# Rectifire__PFC__Evaluation_Board.net
KiCad netlist of a schematic drawn in Altium Designer
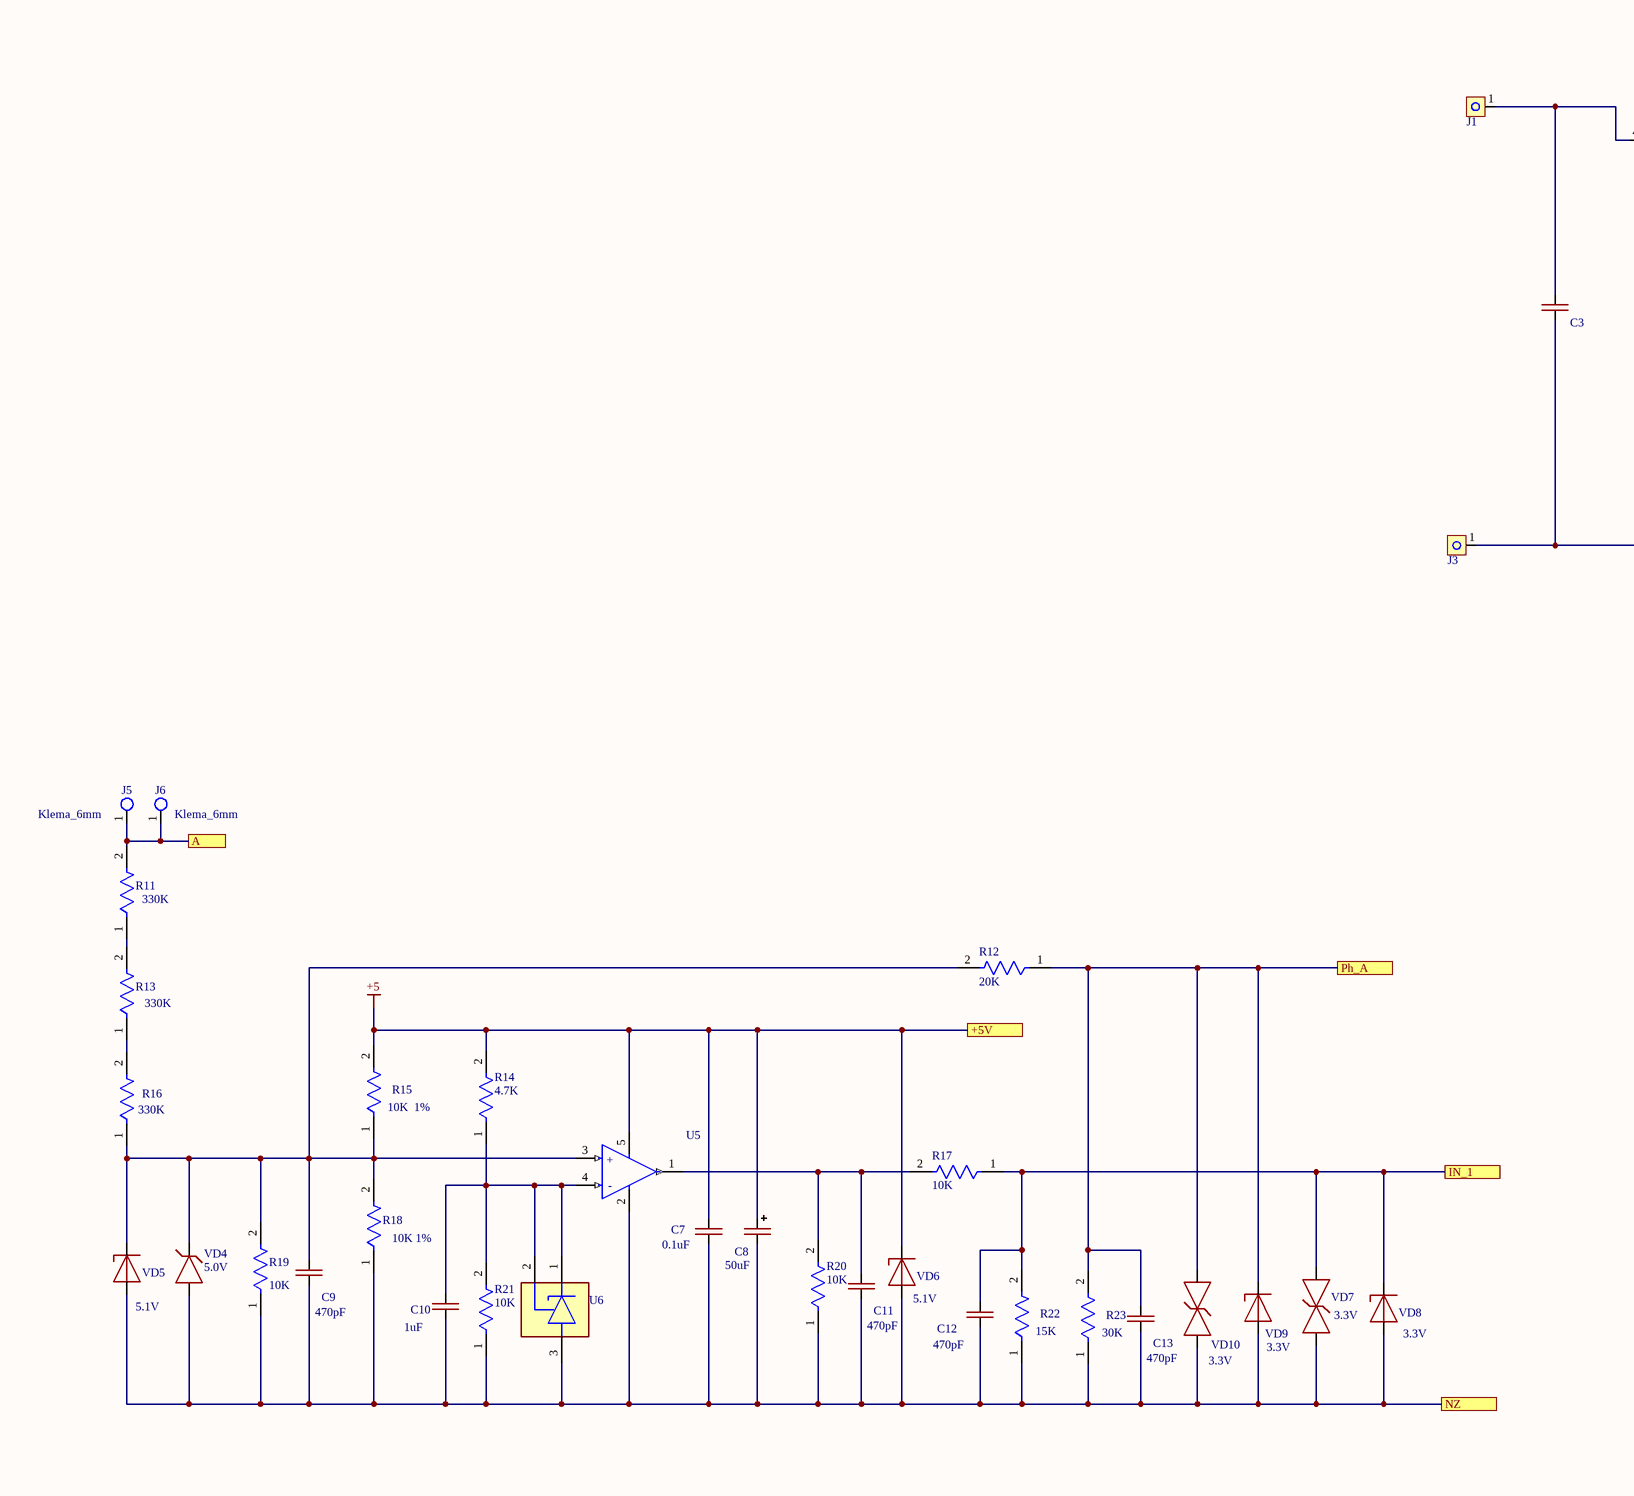
[diagram p0: Rectifire_(PFC)_Evaluation_Board.SchDoc, top left]
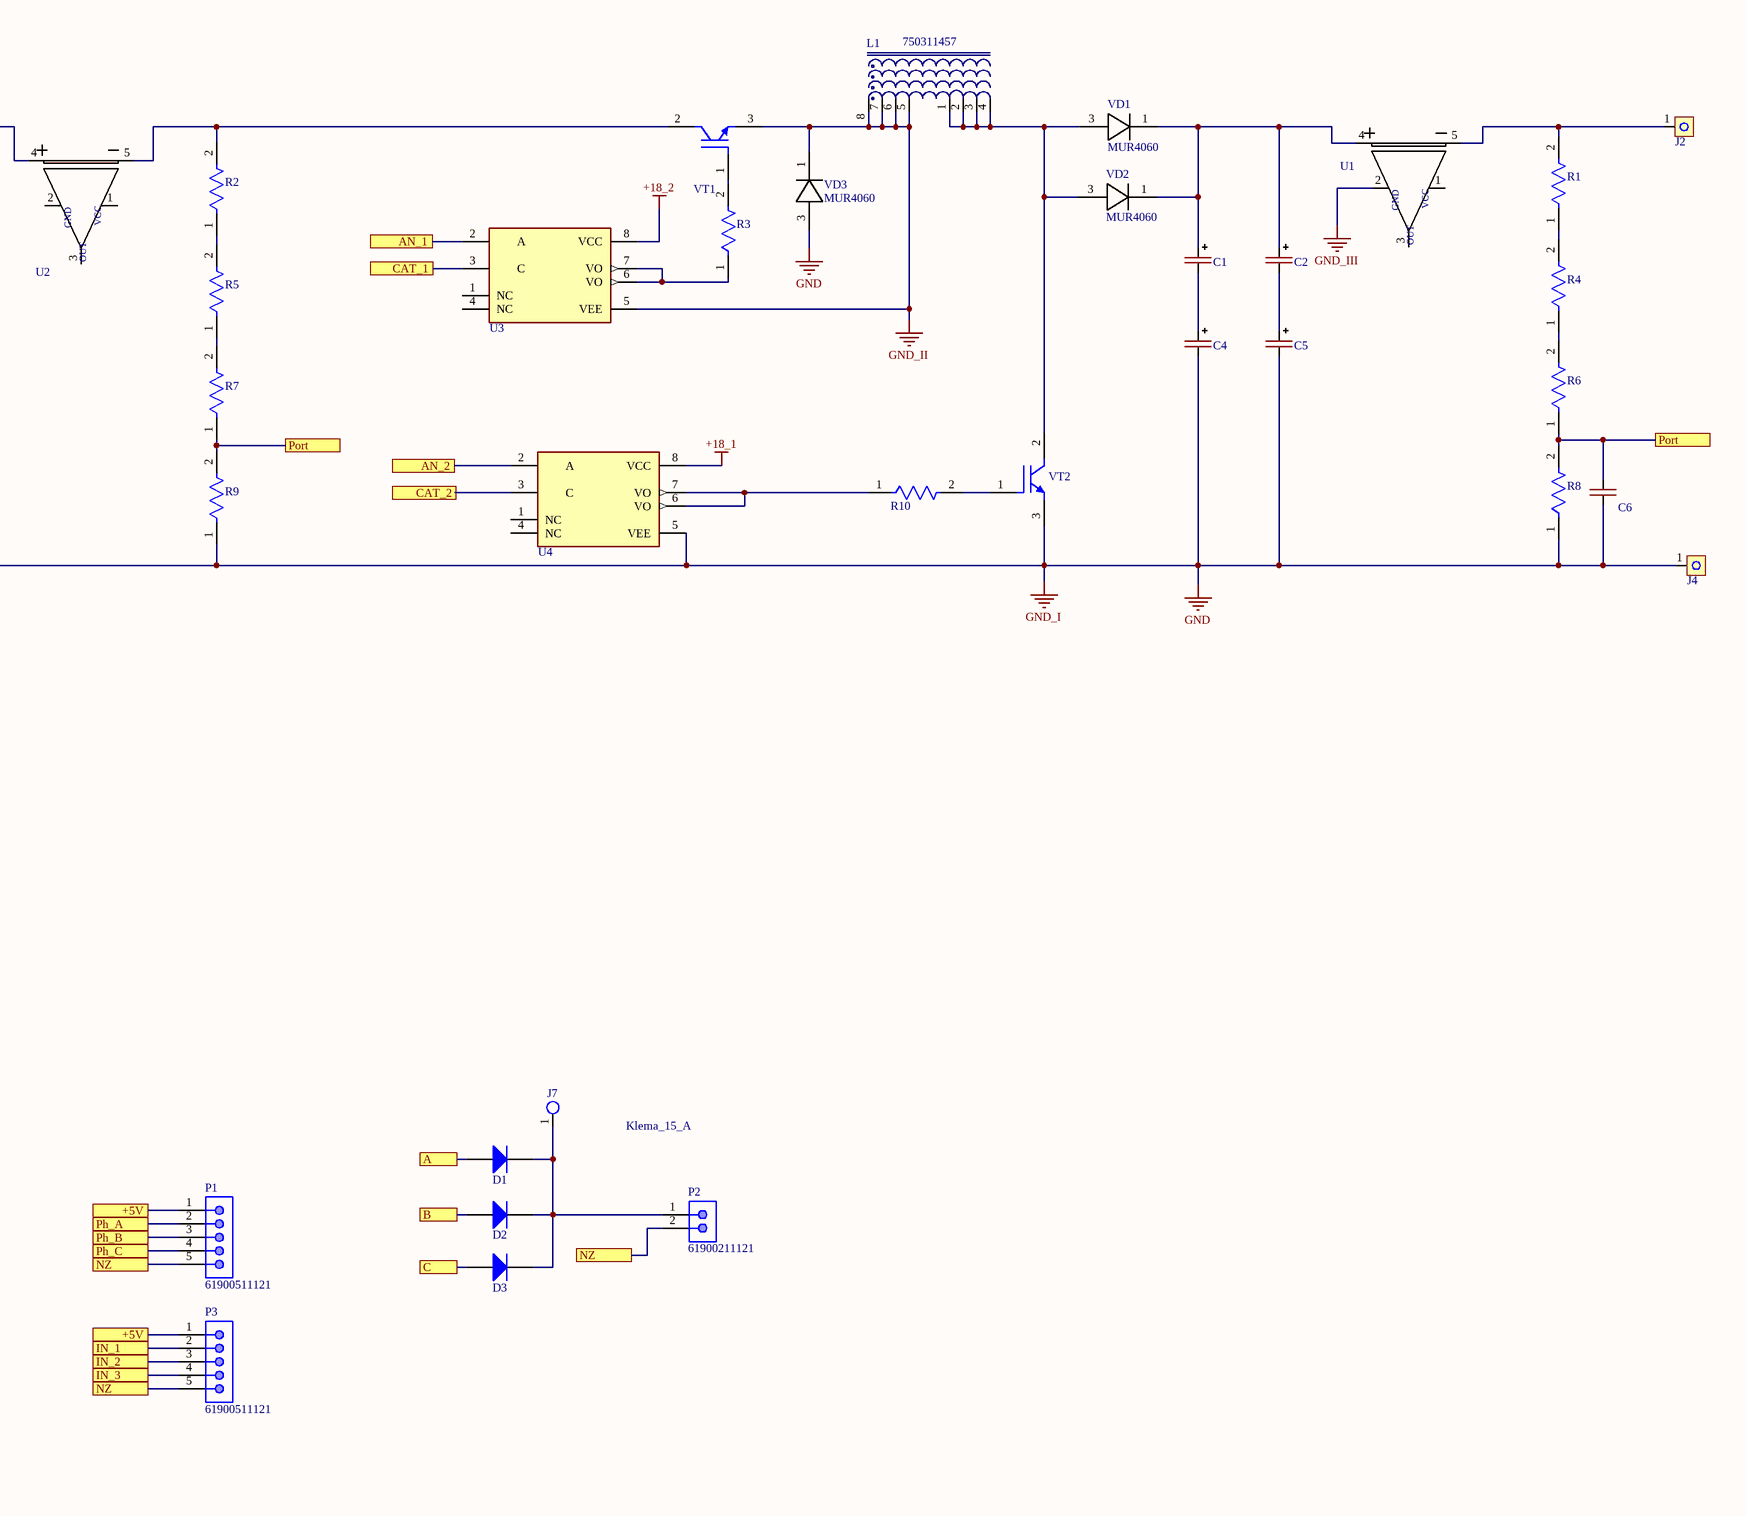
[diagram p1: Rectifire_(PFC)_Evaluation_Board.SchDoc, top right]
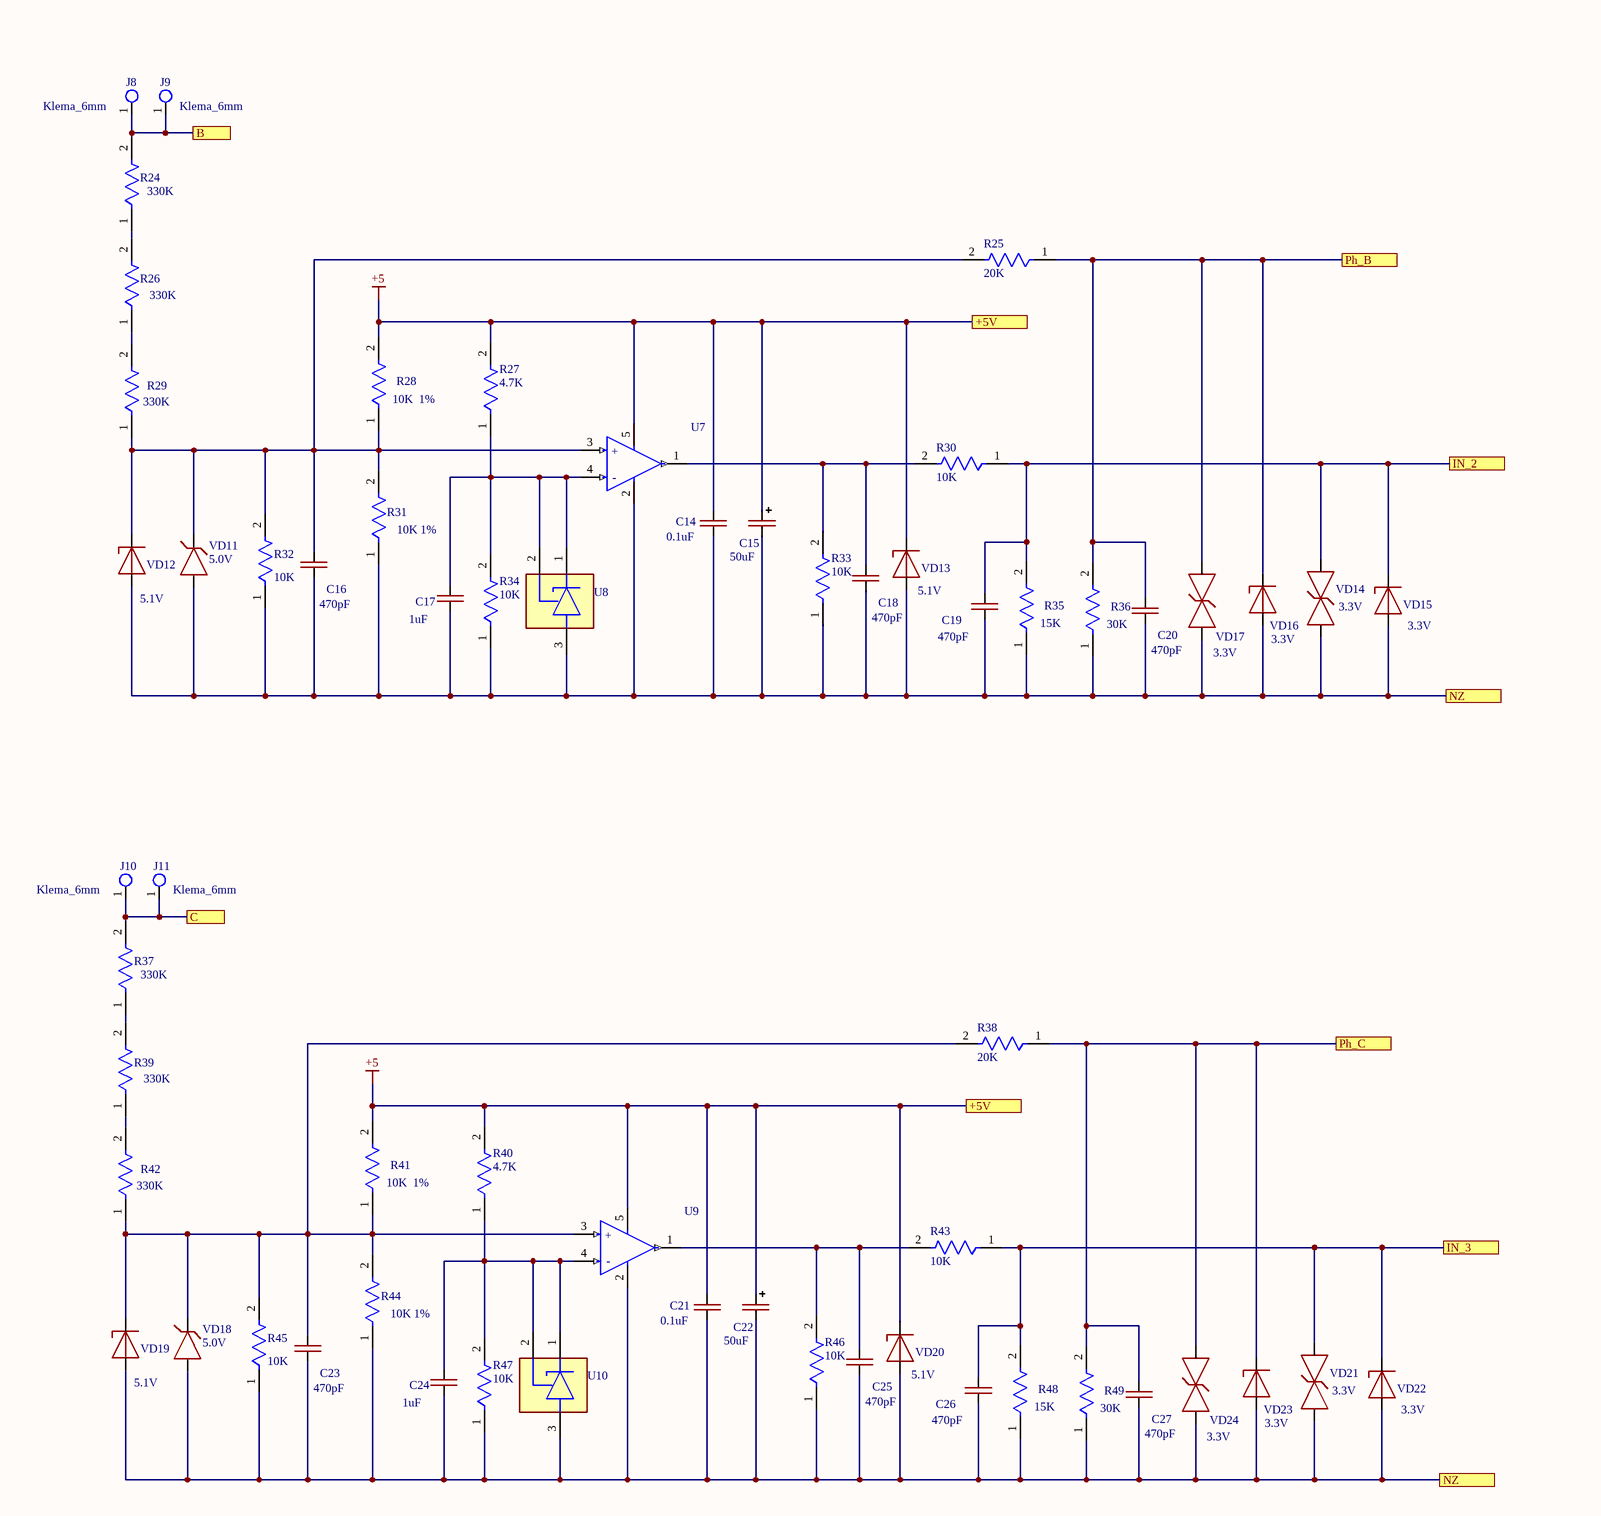
[diagram p2: Rectifire_(PFC)_Evaluation_Board.SchDoc, bottom left]

(export (version "E")
  (design (tool "Eeschema 10.0.6"))
  (components
    (comp (ref "C1")
      (value "CAP-POLAR")
      (footprint "CAP 100uF_500V 22x40mm")
      (libsource (lib "PASSIVE_COMPONENTS") (part "CAP-POLAR"))
    )
    (comp (ref "C2")
      (value "CAP-POLAR")
      (footprint "CAP 100uF_500V 22x40mm")
      (libsource (lib "PASSIVE_COMPONENTS") (part "CAP-POLAR"))
    )
    (comp (ref "C3")
      (value "CAP-NON-POLAR")
      (footprint "CAP_4.7uF_630V")
      (libsource (lib "PASSIVE_COMPONENTS") (part "CAP-NON-POLAR"))
    )
    (comp (ref "C4")
      (value "CAP-POLAR")
      (footprint "CAP 100uF_500V 22x40mm")
      (libsource (lib "PASSIVE_COMPONENTS") (part "CAP-POLAR"))
    )
    (comp (ref "C5")
      (value "CAP-POLAR")
      (footprint "CAP 100uF_500V 22x40mm")
      (libsource (lib "PASSIVE_COMPONENTS") (part "CAP-POLAR"))
    )
    (comp (ref "C6")
      (value "CAP-NON-POLAR")
      (footprint "CAP-0805")
      (libsource (lib "PASSIVE_COMPONENTS") (part "CAP-NON-POLAR"))
    )
    (comp (ref "C7")
      (value "0.1uF")
      (footprint "CAP-0805")
      (libsource (lib "PASSIVE_COMPONENTS") (part "CAP-NON-POLAR"))
    )
    (comp (ref "C8")
      (value "50uF")
      (footprint "CAP-TAN-D")
      (libsource (lib "PASSIVE_COMPONENTS") (part "CAP-POLAR"))
    )
    (comp (ref "C9")
      (value "470pF")
      (footprint "CAP-0805")
      (libsource (lib "PASSIVE_COMPONENTS") (part "CAP-NON-POLAR"))
    )
    (comp (ref "C10")
      (value "1uF")
      (footprint "CAP-0805")
      (libsource (lib "PASSIVE_COMPONENTS") (part "CAP-NON-POLAR"))
    )
    (comp (ref "C11")
      (value "470pF")
      (footprint "CAP-0805")
      (libsource (lib "PASSIVE_COMPONENTS") (part "CAP-NON-POLAR"))
    )
    (comp (ref "C12")
      (value "470pF")
      (footprint "CAP-0805")
      (libsource (lib "PASSIVE_COMPONENTS") (part "CAP-NON-POLAR"))
    )
    (comp (ref "C13")
      (value "470pF")
      (footprint "CAP-0805")
      (libsource (lib "PASSIVE_COMPONENTS") (part "CAP-NON-POLAR"))
    )
    (comp (ref "C14")
      (value "0.1uF")
      (footprint "CAP-0805")
      (libsource (lib "PASSIVE_COMPONENTS") (part "CAP-NON-POLAR"))
    )
    (comp (ref "C15")
      (value "50uF")
      (footprint "CAP-TAN-D")
      (libsource (lib "PASSIVE_COMPONENTS") (part "CAP-POLAR"))
    )
    (comp (ref "C16")
      (value "470pF")
      (footprint "CAP-0805")
      (libsource (lib "PASSIVE_COMPONENTS") (part "CAP-NON-POLAR"))
    )
    (comp (ref "C17")
      (value "1uF")
      (footprint "CAP-0805")
      (libsource (lib "PASSIVE_COMPONENTS") (part "CAP-NON-POLAR"))
    )
    (comp (ref "C18")
      (value "470pF")
      (footprint "CAP-0805")
      (libsource (lib "PASSIVE_COMPONENTS") (part "CAP-NON-POLAR"))
    )
    (comp (ref "C19")
      (value "470pF")
      (footprint "CAP-0805")
      (libsource (lib "PASSIVE_COMPONENTS") (part "CAP-NON-POLAR"))
    )
    (comp (ref "C20")
      (value "470pF")
      (footprint "CAP-0805")
      (libsource (lib "PASSIVE_COMPONENTS") (part "CAP-NON-POLAR"))
    )
    (comp (ref "C21")
      (value "0.1uF")
      (footprint "CAP-0805")
      (libsource (lib "PASSIVE_COMPONENTS") (part "CAP-NON-POLAR"))
    )
    (comp (ref "C22")
      (value "50uF")
      (footprint "CAP-TAN-D")
      (libsource (lib "PASSIVE_COMPONENTS") (part "CAP-POLAR"))
    )
    (comp (ref "C23")
      (value "470pF")
      (footprint "CAP-0805")
      (libsource (lib "PASSIVE_COMPONENTS") (part "CAP-NON-POLAR"))
    )
    (comp (ref "C24")
      (value "1uF")
      (footprint "CAP-0805")
      (libsource (lib "PASSIVE_COMPONENTS") (part "CAP-NON-POLAR"))
    )
    (comp (ref "C25")
      (value "470pF")
      (footprint "CAP-0805")
      (libsource (lib "PASSIVE_COMPONENTS") (part "CAP-NON-POLAR"))
    )
    (comp (ref "C26")
      (value "470pF")
      (footprint "CAP-0805")
      (libsource (lib "PASSIVE_COMPONENTS") (part "CAP-NON-POLAR"))
    )
    (comp (ref "C27")
      (value "470pF")
      (footprint "CAP-0805")
      (libsource (lib "PASSIVE_COMPONENTS") (part "CAP-NON-POLAR"))
    )
    (comp (ref "D1")
      (value "FR-207")
      (footprint "FP-DO-201AD-MFG")
      (description "FR207")
      (libsource (lib "Diodes") (part "FR-207"))
    )
    (comp (ref "D2")
      (value "FR-207")
      (footprint "FP-DO-201AD-MFG")
      (description "FR207")
      (libsource (lib "Diodes") (part "FR-207"))
    )
    (comp (ref "D3")
      (value "FR-207")
      (footprint "FP-DO-201AD-MFG")
      (description "FR207")
      (libsource (lib "Diodes") (part "FR-207"))
    )
    (comp (ref "J1")
      (value "MG_136_HT")
      (footprint "Conn_MEIGAN_MG136HT")
      (libsource (lib "Connectors") (part "Connector_MEIGAN_MG136HT"))
    )
    (comp (ref "J2")
      (value "MG_136_HT")
      (footprint "Conn_MEIGAN_MG136HT")
      (libsource (lib "") (part "Connector_MEIGAN_MG136HT_1"))
    )
    (comp (ref "J3")
      (value "MG_136_HT")
      (footprint "Conn_MEIGAN_MG136HT")
      (libsource (lib "Connectors") (part "Connector_MEIGAN_MG136HT"))
    )
    (comp (ref "J4")
      (value "MG_136_HT")
      (footprint "Conn_MEIGAN_MG136HT")
      (libsource (lib "") (part "Connector_MEIGAN_MG136HT_1"))
    )
    (comp (ref "J5")
      (value "Klema_6mm")
      (footprint "Connector_6mm")
      (libsource (lib "Connectors") (part "Klema_15_A"))
    )
    (comp (ref "J6")
      (value "Klema_6mm")
      (footprint "Connector_6mm")
      (libsource (lib "Connectors") (part "Klema_15_A"))
    )
    (comp (ref "J7")
      (value "Klema_15_A")
      (footprint "Klema_PCB_15A")
      (libsource (lib "Connectors") (part "Klema_15_A"))
    )
    (comp (ref "J8")
      (value "Klema_6mm")
      (footprint "Connector_6mm")
      (libsource (lib "Connectors") (part "Klema_15_A"))
    )
    (comp (ref "J9")
      (value "Klema_6mm")
      (footprint "Connector_6mm")
      (libsource (lib "Connectors") (part "Klema_15_A"))
    )
    (comp (ref "J10")
      (value "Klema_6mm")
      (footprint "Connector_6mm")
      (libsource (lib "Connectors") (part "Klema_15_A"))
    )
    (comp (ref "J11")
      (value "Klema_6mm")
      (footprint "Connector_6mm")
      (libsource (lib "Connectors") (part "Klema_15_A"))
    )
    (comp (ref "L1")
      (value "750311457")
      (footprint "Drossel")
      (description "Drosel")
      (fields (field (name "MANUFACTURER") "Wuerth Elektronik"))
      (libsource (lib "Transformers") (part "DROSEL"))
    )
    (comp (ref "P1")
      (value "61900511121")
      (footprint "61900511121")
      (description "WR-WTB THT Male Vertical Locking Header, pitch 2.54mm, 5p")
      (fields (field (name "PUBLISHER") "Wurth Elektronik"))
      (libsource (lib "Altium_WR-WTB (rev20a)") (part "61900511121"))
    )
    (comp (ref "P2")
      (value "61900211121")
      (footprint "61900211121")
      (description "WR-WTB THT Male Vertical Locking Header, pitch 2.54mm, 2p")
      (fields (field (name "PUBLISHER") "Wurth Elektronik"))
      (libsource (lib "Altium_WR-WTB (rev20a)") (part "61900211121"))
    )
    (comp (ref "P3")
      (value "61900511121")
      (footprint "61900511121")
      (description "WR-WTB THT Male Vertical Locking Header, pitch 2.54mm, 5p")
      (fields (field (name "PUBLISHER") "Wurth Elektronik"))
      (libsource (lib "Altium_WR-WTB (rev20a)") (part "61900511121"))
    )
    (comp (ref "R1")
      (value "RES_1210")
      (footprint "RES_SMD_1210_IPC_B")
      (libsource (lib "PASSIVE_COMPONENTS") (part "RES_1210"))
    )
    (comp (ref "R2")
      (value "RES_1210")
      (footprint "RES_SMD_1210_IPC_B")
      (libsource (lib "PASSIVE_COMPONENTS") (part "RES_1210"))
    )
    (comp (ref "R3")
      (value "RES_1210")
      (footprint "RES_SMD_1210_IPC_B")
      (libsource (lib "PASSIVE_COMPONENTS") (part "RES_1210"))
    )
    (comp (ref "R4")
      (value "RES_1210")
      (footprint "RES_SMD_1210_IPC_B")
      (libsource (lib "PASSIVE_COMPONENTS") (part "RES_1210"))
    )
    (comp (ref "R5")
      (value "RES_1210")
      (footprint "RES_SMD_1210_IPC_B")
      (libsource (lib "PASSIVE_COMPONENTS") (part "RES_1210"))
    )
    (comp (ref "R6")
      (value "RES_1210")
      (footprint "RES_SMD_1210_IPC_B")
      (libsource (lib "PASSIVE_COMPONENTS") (part "RES_1210"))
    )
    (comp (ref "R7")
      (value "RES_1210")
      (footprint "RES_SMD_1210_IPC_B")
      (libsource (lib "PASSIVE_COMPONENTS") (part "RES_1210"))
    )
    (comp (ref "R8")
      (value "RES_1210")
      (footprint "RES_SMD_1210_IPC_B")
      (libsource (lib "PASSIVE_COMPONENTS") (part "RES_1210"))
    )
    (comp (ref "R9")
      (value "RES_1210")
      (footprint "RES_SMD_1210_IPC_B")
      (libsource (lib "PASSIVE_COMPONENTS") (part "RES_1210"))
    )
    (comp (ref "R10")
      (value "RES_1210")
      (footprint "RES_SMD_1210_IPC_B")
      (libsource (lib "PASSIVE_COMPONENTS") (part "RES_1210"))
    )
    (comp (ref "R11")
      (value "330K")
      (footprint "RES_SMD_1210_IPC_B")
      (libsource (lib "PASSIVE_COMPONENTS") (part "RES_1210"))
    )
    (comp (ref "R12")
      (value "20K")
      (footprint "RES-0805")
      (libsource (lib "PASSIVE_COMPONENTS") (part "RES-CONST"))
    )
    (comp (ref "R13")
      (value "330K")
      (footprint "RES_SMD_1210_IPC_B")
      (libsource (lib "PASSIVE_COMPONENTS") (part "RES_1210"))
    )
    (comp (ref "R14")
      (value "4.7K")
      (footprint "RES-0805")
      (libsource (lib "PASSIVE_COMPONENTS") (part "RES-CONST"))
    )
    (comp (ref "R15")
      (value "10K  1%")
      (footprint "RES-0805")
      (description "10K")
      (libsource (lib "PASSIVE_COMPONENTS") (part "RES-CONST"))
    )
    (comp (ref "R16")
      (value "330K")
      (footprint "RES_SMD_1210_IPC_B")
      (libsource (lib "PASSIVE_COMPONENTS") (part "RES_1210"))
    )
    (comp (ref "R17")
      (value "10K")
      (footprint "RES-0805")
      (libsource (lib "PASSIVE_COMPONENTS") (part "RES-CONST"))
    )
    (comp (ref "R18")
      (value "10K 1%")
      (footprint "RES-0805")
      (description "10K")
      (libsource (lib "PASSIVE_COMPONENTS") (part "RES-CONST"))
    )
    (comp (ref "R19")
      (value "10K")
      (footprint "RES_SMD_1210_IPC_B")
      (libsource (lib "PASSIVE_COMPONENTS") (part "RES_1210"))
    )
    (comp (ref "R20")
      (value "10K")
      (footprint "RES-0805")
      (libsource (lib "PASSIVE_COMPONENTS") (part "RES-CONST"))
    )
    (comp (ref "R21")
      (value "10K")
      (footprint "RES-0805")
      (libsource (lib "PASSIVE_COMPONENTS") (part "RES-CONST"))
    )
    (comp (ref "R22")
      (value "15K")
      (footprint "RES-0805")
      (libsource (lib "PASSIVE_COMPONENTS") (part "RES-CONST"))
    )
    (comp (ref "R23")
      (value "30K")
      (footprint "RES-0805")
      (libsource (lib "PASSIVE_COMPONENTS") (part "RES-CONST"))
    )
    (comp (ref "R24")
      (value "330K")
      (footprint "RES_SMD_1210_IPC_B")
      (libsource (lib "PASSIVE_COMPONENTS") (part "RES_1210"))
    )
    (comp (ref "R25")
      (value "20K")
      (footprint "RES-0805")
      (libsource (lib "PASSIVE_COMPONENTS") (part "RES-CONST"))
    )
    (comp (ref "R26")
      (value "330K")
      (footprint "RES_SMD_1210_IPC_B")
      (libsource (lib "PASSIVE_COMPONENTS") (part "RES_1210"))
    )
    (comp (ref "R27")
      (value "4.7K")
      (footprint "RES-0805")
      (libsource (lib "PASSIVE_COMPONENTS") (part "RES-CONST"))
    )
    (comp (ref "R28")
      (value "10K  1%")
      (footprint "RES-0805")
      (description "10K")
      (libsource (lib "PASSIVE_COMPONENTS") (part "RES-CONST"))
    )
    (comp (ref "R29")
      (value "330K")
      (footprint "RES_SMD_1210_IPC_B")
      (libsource (lib "PASSIVE_COMPONENTS") (part "RES_1210"))
    )
    (comp (ref "R30")
      (value "10K")
      (footprint "RES-0805")
      (libsource (lib "PASSIVE_COMPONENTS") (part "RES-CONST"))
    )
    (comp (ref "R31")
      (value "10K 1%")
      (footprint "RES-0805")
      (description "10K")
      (libsource (lib "PASSIVE_COMPONENTS") (part "RES-CONST"))
    )
    (comp (ref "R32")
      (value "10K")
      (footprint "RES_SMD_1210_IPC_B")
      (libsource (lib "PASSIVE_COMPONENTS") (part "RES_1210"))
    )
    (comp (ref "R33")
      (value "10K")
      (footprint "RES-0805")
      (libsource (lib "PASSIVE_COMPONENTS") (part "RES-CONST"))
    )
    (comp (ref "R34")
      (value "10K")
      (footprint "RES-0805")
      (libsource (lib "PASSIVE_COMPONENTS") (part "RES-CONST"))
    )
    (comp (ref "R35")
      (value "15K")
      (footprint "RES-0805")
      (libsource (lib "PASSIVE_COMPONENTS") (part "RES-CONST"))
    )
    (comp (ref "R36")
      (value "30K")
      (footprint "RES-0805")
      (libsource (lib "PASSIVE_COMPONENTS") (part "RES-CONST"))
    )
    (comp (ref "R37")
      (value "330K")
      (footprint "RES_SMD_1210_IPC_B")
      (libsource (lib "PASSIVE_COMPONENTS") (part "RES_1210"))
    )
    (comp (ref "R38")
      (value "20K")
      (footprint "RES-0805")
      (libsource (lib "PASSIVE_COMPONENTS") (part "RES-CONST"))
    )
    (comp (ref "R39")
      (value "330K")
      (footprint "RES_SMD_1210_IPC_B")
      (libsource (lib "PASSIVE_COMPONENTS") (part "RES_1210"))
    )
    (comp (ref "R40")
      (value "4.7K")
      (footprint "RES-0805")
      (libsource (lib "PASSIVE_COMPONENTS") (part "RES-CONST"))
    )
    (comp (ref "R41")
      (value "10K  1%")
      (footprint "RES-0805")
      (description "10K")
      (libsource (lib "PASSIVE_COMPONENTS") (part "RES-CONST"))
    )
    (comp (ref "R42")
      (value "330K")
      (footprint "RES_SMD_1210_IPC_B")
      (libsource (lib "PASSIVE_COMPONENTS") (part "RES_1210"))
    )
    (comp (ref "R43")
      (value "10K")
      (footprint "RES-0805")
      (libsource (lib "PASSIVE_COMPONENTS") (part "RES-CONST"))
    )
    (comp (ref "R44")
      (value "10K 1%")
      (footprint "RES-0805")
      (description "10K")
      (libsource (lib "PASSIVE_COMPONENTS") (part "RES-CONST"))
    )
    (comp (ref "R45")
      (value "10K")
      (footprint "RES_SMD_1210_IPC_B")
      (libsource (lib "PASSIVE_COMPONENTS") (part "RES_1210"))
    )
    (comp (ref "R46")
      (value "10K")
      (footprint "RES-0805")
      (libsource (lib "PASSIVE_COMPONENTS") (part "RES-CONST"))
    )
    (comp (ref "R47")
      (value "10K")
      (footprint "RES-0805")
      (libsource (lib "PASSIVE_COMPONENTS") (part "RES-CONST"))
    )
    (comp (ref "R48")
      (value "15K")
      (footprint "RES-0805")
      (libsource (lib "PASSIVE_COMPONENTS") (part "RES-CONST"))
    )
    (comp (ref "R49")
      (value "30K")
      (footprint "RES-0805")
      (libsource (lib "PASSIVE_COMPONENTS") (part "RES-CONST"))
    )
    (comp (ref "U1")
      (value "ACS758")
      (footprint "ACS758-100")
      (libsource (lib "Integrated_Circuts") (part "ACS758"))
    )
    (comp (ref "U2")
      (value "ACS758")
      (footprint "ACS758-100")
      (libsource (lib "Integrated_Circuts") (part "ACS758"))
    )
    (comp (ref "U3")
      (value "HCPL-3120")
      (footprint "HCPL-3120")
      (libsource (lib "Integrated_Circuts") (part "HCPL-3120"))
    )
    (comp (ref "U4")
      (value "HCPL-3120")
      (footprint "HCPL-3120")
      (libsource (lib "Integrated_Circuts") (part "HCPL-3120"))
    )
    (comp (ref "U5")
      (value "~")
      (footprint "SOT-23-5")
      (description "IC OPAMP GP 1 CIRCUIT SOT23-5")
      (fields (field (name "VOLTAGE") "6V"))
      (libsource (lib "Integrated_Circuts") (part "MCP6001T"))
    )
    (comp (ref "U6")
      (value "TL431")
      (footprint "TL431_SOT-23-3(A)")
      (description "TL431_SOT-23-3")
      (libsource (lib "Diodes") (part "TL431_SOT-23-3"))
    )
    (comp (ref "U7")
      (value "~")
      (footprint "SOT-23-5")
      (description "IC OPAMP GP 1 CIRCUIT SOT23-5")
      (fields (field (name "VOLTAGE") "6V"))
      (libsource (lib "Integrated_Circuts") (part "MCP6001T"))
    )
    (comp (ref "U8")
      (value "TL431")
      (footprint "TL431_SOT-23-3(A)")
      (description "TL431_SOT-23-3")
      (libsource (lib "Diodes") (part "TL431_SOT-23-3"))
    )
    (comp (ref "U9")
      (value "~")
      (footprint "SOT-23-5")
      (description "IC OPAMP GP 1 CIRCUIT SOT23-5")
      (fields (field (name "VOLTAGE") "6V"))
      (libsource (lib "Integrated_Circuts") (part "MCP6001T"))
    )
    (comp (ref "U10")
      (value "TL431")
      (footprint "TL431_SOT-23-3(A)")
      (description "TL431_SOT-23-3")
      (libsource (lib "Diodes") (part "TL431_SOT-23-3"))
    )
    (comp (ref "VD1") (value "MUR4060") (footprint "TO-247-2") (libsource (lib "Diodes") (part "MUR4060")))
    (comp (ref "VD2") (value "MUR4060") (footprint "TO-247-2") (libsource (lib "Diodes") (part "MUR4060")))
    (comp (ref "VD3") (value "MUR4060") (footprint "TO-247-2") (libsource (lib "Diodes") (part "MUR4060")))
    (comp (ref "VD4") (value "5.0V") (footprint "SOD-323") (libsource (lib "Diodes") (part "SMBJ15A")))
    (comp (ref "VD5") (value "5.1V") (footprint "DIOD-SOD123-2_V") (libsource (lib "Diodes") (part "ZENER")))
    (comp (ref "VD6") (value "5.1V") (footprint "DIOD-SOD123-2_V") (libsource (lib "Diodes") (part "ZENER")))
    (comp (ref "VD7") (value "3.3V") (footprint "DO-214AA") (libsource (lib "Diodes") (part "Suppressor")))
    (comp (ref "VD8") (value "3.3V") (footprint "DIOD-SOD123-2_V") (libsource (lib "Diodes") (part "ZENER")))
    (comp (ref "VD9") (value "3.3V") (footprint "DIOD-SOD123-2_V") (libsource (lib "Diodes") (part "ZENER")))
    (comp (ref "VD10") (value "3.3V") (footprint "DO-214AA") (libsource (lib "Diodes") (part "Suppressor")))
    (comp (ref "VD11") (value "5.0V") (footprint "SOD-323") (libsource (lib "Diodes") (part "SMBJ15A")))
    (comp (ref "VD12") (value "5.1V") (footprint "DIOD-SOD123-2_V") (libsource (lib "Diodes") (part "ZENER")))
    (comp (ref "VD13") (value "5.1V") (footprint "DIOD-SOD123-2_V") (libsource (lib "Diodes") (part "ZENER")))
    (comp (ref "VD14") (value "3.3V") (footprint "DO-214AA") (libsource (lib "Diodes") (part "Suppressor")))
    (comp (ref "VD15") (value "3.3V") (footprint "DIOD-SOD123-2_V") (libsource (lib "Diodes") (part "ZENER")))
    (comp (ref "VD16") (value "3.3V") (footprint "DIOD-SOD123-2_V") (libsource (lib "Diodes") (part "ZENER")))
    (comp (ref "VD17") (value "3.3V") (footprint "DO-214AA") (libsource (lib "Diodes") (part "Suppressor")))
    (comp (ref "VD18") (value "5.0V") (footprint "SOD-323") (libsource (lib "Diodes") (part "SMBJ15A")))
    (comp (ref "VD19") (value "5.1V") (footprint "DIOD-SOD123-2_V") (libsource (lib "Diodes") (part "ZENER")))
    (comp (ref "VD20") (value "5.1V") (footprint "DIOD-SOD123-2_V") (libsource (lib "Diodes") (part "ZENER")))
    (comp (ref "VD21") (value "3.3V") (footprint "DO-214AA") (libsource (lib "Diodes") (part "Suppressor")))
    (comp (ref "VD22") (value "3.3V") (footprint "DIOD-SOD123-2_V") (libsource (lib "Diodes") (part "ZENER")))
    (comp (ref "VD23") (value "3.3V") (footprint "DIOD-SOD123-2_V") (libsource (lib "Diodes") (part "ZENER")))
    (comp (ref "VD24") (value "3.3V") (footprint "DO-214AA") (libsource (lib "Diodes") (part "Suppressor")))
    (comp (ref "VT1")
      (value "IGBT 60N120T")
      (footprint "TO-264-3")
      (description "IGBT 60N120T TO-264-3")
      (libsource (lib "Transistors") (part "IGBT 60N120T"))
    )
    (comp (ref "VT2")
      (value "IGBT 60N120T")
      (footprint "TO-264-3")
      (description "IGBT 60N120T TO-264-3")
      (libsource (lib "Transistors") (part "IGBT 60N120T"))
    )
  )
  (nets
    (net (code "1") (name "+5") (class "Default")
      (node (ref "C14") (pin "2") (pinfunction "2_2") (pintype "passive"))
      (node (ref "C15") (pin "1") (pinfunction "+_1") (pintype "passive"))
      (node (ref "C21") (pin "2") (pinfunction "2_2") (pintype "passive"))
      (node (ref "C22") (pin "1") (pinfunction "+_1") (pintype "passive"))
      (node (ref "C7") (pin "2") (pinfunction "2_2") (pintype "passive"))
      (node (ref "C8") (pin "1") (pinfunction "+_1") (pintype "passive"))
      (node (ref "P1") (pin "1") (pinfunction "1_1") (pintype "passive"))
      (node (ref "P3") (pin "1") (pinfunction "1_1") (pintype "passive"))
      (node (ref "R14") (pin "2") (pinfunction "2_2") (pintype "passive"))
      (node (ref "R15") (pin "2") (pinfunction "2_2") (pintype "passive"))
      (node (ref "R27") (pin "2") (pinfunction "2_2") (pintype "passive"))
      (node (ref "R28") (pin "2") (pinfunction "2_2") (pintype "passive"))
      (node (ref "R40") (pin "2") (pinfunction "2_2") (pintype "passive"))
      (node (ref "R41") (pin "2") (pinfunction "2_2") (pintype "passive"))
      (node (ref "U5") (pin "5") (pinfunction "VDD_5") (pintype "power_in"))
      (node (ref "U7") (pin "5") (pinfunction "VDD_5") (pintype "power_in"))
      (node (ref "U9") (pin "5") (pinfunction "VDD_5") (pintype "power_in"))
      (node (ref "VD13") (pin "1") (pinfunction "C_1") (pintype "passive"))
      (node (ref "VD20") (pin "1") (pinfunction "C_1") (pintype "passive"))
      (node (ref "VD6") (pin "1") (pinfunction "C_1") (pintype "passive"))
    )
    (net (code "2") (name "+18_1") (class "Default")
      (node (ref "U4") (pin "8") (pinfunction "VCC_8") (pintype "power_in"))
    )
    (net (code "3") (name "+18_2") (class "Default")
      (node (ref "U3") (pin "8") (pinfunction "VCC_8") (pintype "power_in"))
    )
    (net (code "4") (name "/A") (class "Default")
      (node (ref "D1") (pin "2") (pinfunction "A_2") (pintype "passive"))
      (node (ref "J5") (pin "1") (pinfunction "0_1") (pintype "passive"))
      (node (ref "J6") (pin "1") (pinfunction "0_1") (pintype "passive"))
      (node (ref "R11") (pin "2") (pinfunction "2_2") (pintype "passive"))
    )
    (net (code "5") (name "/AN_1") (class "Default")
      (node (ref "U3") (pin "2") (pinfunction "A_2") (pintype "passive"))
    )
    (net (code "6") (name "/AN_2") (class "Default")
      (node (ref "U4") (pin "2") (pinfunction "A_2") (pintype "passive"))
    )
    (net (code "7") (name "/B") (class "Default")
      (node (ref "D2") (pin "2") (pinfunction "A_2") (pintype "passive"))
      (node (ref "J8") (pin "1") (pinfunction "0_1") (pintype "passive"))
      (node (ref "J9") (pin "1") (pinfunction "0_1") (pintype "passive"))
      (node (ref "R24") (pin "2") (pinfunction "2_2") (pintype "passive"))
    )
    (net (code "8") (name "/C") (class "Default")
      (node (ref "D3") (pin "2") (pinfunction "A_2") (pintype "passive"))
      (node (ref "J10") (pin "1") (pinfunction "0_1") (pintype "passive"))
      (node (ref "J11") (pin "1") (pinfunction "0_1") (pintype "passive"))
      (node (ref "R37") (pin "2") (pinfunction "2_2") (pintype "passive"))
    )
    (net (code "9") (name "/CAT_1") (class "Default")
      (node (ref "U3") (pin "3") (pinfunction "C_3") (pintype "passive"))
    )
    (net (code "10") (name "/CAT_2") (class "Default")
      (node (ref "U4") (pin "3") (pinfunction "C_3") (pintype "passive"))
    )
    (net (code "11") (name "/IN_1") (class "Default")
      (node (ref "C12") (pin "2") (pinfunction "2_2") (pintype "passive"))
      (node (ref "P3") (pin "2") (pinfunction "2_2") (pintype "passive"))
      (node (ref "R17") (pin "1") (pinfunction "1_1") (pintype "passive"))
      (node (ref "R22") (pin "2") (pinfunction "2_2") (pintype "passive"))
      (node (ref "VD7") (pin "2") (pinfunction "A_2") (pintype "passive"))
      (node (ref "VD8") (pin "1") (pinfunction "C_1") (pintype "passive"))
    )
    (net (code "12") (name "/IN_2") (class "Default")
      (node (ref "C19") (pin "2") (pinfunction "2_2") (pintype "passive"))
      (node (ref "P3") (pin "3") (pinfunction "3_3") (pintype "passive"))
      (node (ref "R30") (pin "1") (pinfunction "1_1") (pintype "passive"))
      (node (ref "R35") (pin "2") (pinfunction "2_2") (pintype "passive"))
      (node (ref "VD14") (pin "2") (pinfunction "A_2") (pintype "passive"))
      (node (ref "VD15") (pin "1") (pinfunction "C_1") (pintype "passive"))
    )
    (net (code "13") (name "/IN_3") (class "Default")
      (node (ref "C26") (pin "2") (pinfunction "2_2") (pintype "passive"))
      (node (ref "P3") (pin "4") (pinfunction "4_4") (pintype "passive"))
      (node (ref "R43") (pin "1") (pinfunction "1_1") (pintype "passive"))
      (node (ref "R48") (pin "2") (pinfunction "2_2") (pintype "passive"))
      (node (ref "VD21") (pin "2") (pinfunction "A_2") (pintype "passive"))
      (node (ref "VD22") (pin "1") (pinfunction "C_1") (pintype "passive"))
    )
    (net (code "14") (name "/NZ") (class "Default")
      (node (ref "C10") (pin "1") (pinfunction "1_1") (pintype "passive"))
      (node (ref "C11") (pin "1") (pinfunction "1_1") (pintype "passive"))
      (node (ref "C12") (pin "1") (pinfunction "1_1") (pintype "passive"))
      (node (ref "C13") (pin "1") (pinfunction "1_1") (pintype "passive"))
      (node (ref "C14") (pin "1") (pinfunction "1_1") (pintype "passive"))
      (node (ref "C15") (pin "2") (pinfunction "-_2") (pintype "passive"))
      (node (ref "C16") (pin "1") (pinfunction "1_1") (pintype "passive"))
      (node (ref "C17") (pin "1") (pinfunction "1_1") (pintype "passive"))
      (node (ref "C18") (pin "1") (pinfunction "1_1") (pintype "passive"))
      (node (ref "C19") (pin "1") (pinfunction "1_1") (pintype "passive"))
      (node (ref "C20") (pin "1") (pinfunction "1_1") (pintype "passive"))
      (node (ref "C21") (pin "1") (pinfunction "1_1") (pintype "passive"))
      (node (ref "C22") (pin "2") (pinfunction "-_2") (pintype "passive"))
      (node (ref "C23") (pin "1") (pinfunction "1_1") (pintype "passive"))
      (node (ref "C24") (pin "1") (pinfunction "1_1") (pintype "passive"))
      (node (ref "C25") (pin "1") (pinfunction "1_1") (pintype "passive"))
      (node (ref "C26") (pin "1") (pinfunction "1_1") (pintype "passive"))
      (node (ref "C27") (pin "1") (pinfunction "1_1") (pintype "passive"))
      (node (ref "C7") (pin "1") (pinfunction "1_1") (pintype "passive"))
      (node (ref "C8") (pin "2") (pinfunction "-_2") (pintype "passive"))
      (node (ref "C9") (pin "1") (pinfunction "1_1") (pintype "passive"))
      (node (ref "P1") (pin "5") (pinfunction "5_5") (pintype "passive"))
      (node (ref "P2") (pin "2") (pinfunction "2_2") (pintype "passive"))
      (node (ref "P3") (pin "5") (pinfunction "5_5") (pintype "passive"))
      (node (ref "R18") (pin "1") (pinfunction "1_1") (pintype "passive"))
      (node (ref "R19") (pin "1") (pinfunction "1_1") (pintype "passive"))
      (node (ref "R20") (pin "1") (pinfunction "1_1") (pintype "passive"))
      (node (ref "R21") (pin "1") (pinfunction "1_1") (pintype "passive"))
      (node (ref "R22") (pin "1") (pinfunction "1_1") (pintype "passive"))
      (node (ref "R23") (pin "1") (pinfunction "1_1") (pintype "passive"))
      (node (ref "R31") (pin "1") (pinfunction "1_1") (pintype "passive"))
      (node (ref "R32") (pin "1") (pinfunction "1_1") (pintype "passive"))
      (node (ref "R33") (pin "1") (pinfunction "1_1") (pintype "passive"))
      (node (ref "R34") (pin "1") (pinfunction "1_1") (pintype "passive"))
      (node (ref "R35") (pin "1") (pinfunction "1_1") (pintype "passive"))
      (node (ref "R36") (pin "1") (pinfunction "1_1") (pintype "passive"))
      (node (ref "R44") (pin "1") (pinfunction "1_1") (pintype "passive"))
      (node (ref "R45") (pin "1") (pinfunction "1_1") (pintype "passive"))
      (node (ref "R46") (pin "1") (pinfunction "1_1") (pintype "passive"))
      (node (ref "R47") (pin "1") (pinfunction "1_1") (pintype "passive"))
      (node (ref "R48") (pin "1") (pinfunction "1_1") (pintype "passive"))
      (node (ref "R49") (pin "1") (pinfunction "1_1") (pintype "passive"))
      (node (ref "U10") (pin "3") (pinfunction "A_3") (pintype "passive"))
      (node (ref "U5") (pin "2") (pinfunction "VSS_2") (pintype "power_in"))
      (node (ref "U6") (pin "3") (pinfunction "A_3") (pintype "passive"))
      (node (ref "U7") (pin "2") (pinfunction "VSS_2") (pintype "power_in"))
      (node (ref "U8") (pin "3") (pinfunction "A_3") (pintype "passive"))
      (node (ref "U9") (pin "2") (pinfunction "VSS_2") (pintype "power_in"))
      (node (ref "VD10") (pin "1") (pinfunction "C_1") (pintype "passive"))
      (node (ref "VD11") (pin "1") (pinfunction "A_1") (pintype "passive"))
      (node (ref "VD12") (pin "2") (pinfunction "A_2") (pintype "passive"))
      (node (ref "VD13") (pin "2") (pinfunction "A_2") (pintype "passive"))
      (node (ref "VD14") (pin "1") (pinfunction "C_1") (pintype "passive"))
      (node (ref "VD15") (pin "2") (pinfunction "A_2") (pintype "passive"))
      (node (ref "VD16") (pin "2") (pinfunction "A_2") (pintype "passive"))
      (node (ref "VD17") (pin "1") (pinfunction "C_1") (pintype "passive"))
      (node (ref "VD18") (pin "1") (pinfunction "A_1") (pintype "passive"))
      (node (ref "VD19") (pin "2") (pinfunction "A_2") (pintype "passive"))
      (node (ref "VD20") (pin "2") (pinfunction "A_2") (pintype "passive"))
      (node (ref "VD21") (pin "1") (pinfunction "C_1") (pintype "passive"))
      (node (ref "VD22") (pin "2") (pinfunction "A_2") (pintype "passive"))
      (node (ref "VD23") (pin "2") (pinfunction "A_2") (pintype "passive"))
      (node (ref "VD24") (pin "1") (pinfunction "C_1") (pintype "passive"))
      (node (ref "VD4") (pin "1") (pinfunction "A_1") (pintype "passive"))
      (node (ref "VD5") (pin "2") (pinfunction "A_2") (pintype "passive"))
      (node (ref "VD6") (pin "2") (pinfunction "A_2") (pintype "passive"))
      (node (ref "VD7") (pin "1") (pinfunction "C_1") (pintype "passive"))
      (node (ref "VD8") (pin "2") (pinfunction "A_2") (pintype "passive"))
      (node (ref "VD9") (pin "2") (pinfunction "A_2") (pintype "passive"))
    )
    (net (code "15") (name "/Ph_A") (class "Default")
      (node (ref "C13") (pin "2") (pinfunction "2_2") (pintype "passive"))
      (node (ref "P1") (pin "2") (pinfunction "2_2") (pintype "passive"))
      (node (ref "R12") (pin "1") (pinfunction "1_1") (pintype "passive"))
      (node (ref "R23") (pin "2") (pinfunction "2_2") (pintype "passive"))
      (node (ref "VD10") (pin "2") (pinfunction "A_2") (pintype "passive"))
      (node (ref "VD9") (pin "1") (pinfunction "C_1") (pintype "passive"))
    )
    (net (code "16") (name "/Ph_B") (class "Default")
      (node (ref "C20") (pin "2") (pinfunction "2_2") (pintype "passive"))
      (node (ref "P1") (pin "3") (pinfunction "3_3") (pintype "passive"))
      (node (ref "R25") (pin "1") (pinfunction "1_1") (pintype "passive"))
      (node (ref "R36") (pin "2") (pinfunction "2_2") (pintype "passive"))
      (node (ref "VD16") (pin "1") (pinfunction "C_1") (pintype "passive"))
      (node (ref "VD17") (pin "2") (pinfunction "A_2") (pintype "passive"))
    )
    (net (code "17") (name "/Ph_C") (class "Default")
      (node (ref "C27") (pin "2") (pinfunction "2_2") (pintype "passive"))
      (node (ref "P1") (pin "4") (pinfunction "4_4") (pintype "passive"))
      (node (ref "R38") (pin "1") (pinfunction "1_1") (pintype "passive"))
      (node (ref "R49") (pin "2") (pinfunction "2_2") (pintype "passive"))
      (node (ref "VD23") (pin "1") (pinfunction "C_1") (pintype "passive"))
      (node (ref "VD24") (pin "2") (pinfunction "A_2") (pintype "passive"))
    )
    (net (code "18") (name "/Port") (class "Default")
      (node (ref "C6") (pin "2") (pinfunction "2_2") (pintype "passive"))
      (node (ref "R6") (pin "1") (pinfunction "1_1") (pintype "passive"))
      (node (ref "R7") (pin "1") (pinfunction "1_1") (pintype "passive"))
      (node (ref "R8") (pin "2") (pinfunction "2_2") (pintype "passive"))
      (node (ref "R9") (pin "2") (pinfunction "2_2") (pintype "passive"))
    )
    (net (code "19") (name "GND") (class "Default")
      (node (ref "C3") (pin "1") (pinfunction "1_1") (pintype "passive"))
      (node (ref "C4") (pin "2") (pinfunction "-_2") (pintype "passive"))
      (node (ref "C5") (pin "2") (pinfunction "-_2") (pintype "passive"))
      (node (ref "C6") (pin "1") (pinfunction "1_1") (pintype "passive"))
      (node (ref "J3") (pin "1") (pinfunction "17_1") (pintype "passive"))
      (node (ref "J4") (pin "1") (pinfunction "17_1") (pintype "passive"))
      (node (ref "R8") (pin "1") (pinfunction "1_1") (pintype "passive"))
      (node (ref "R9") (pin "1") (pinfunction "1_1") (pintype "passive"))
      (node (ref "U4") (pin "5") (pinfunction "VEE_5") (pintype "power_in"))
      (node (ref "VD3") (pin "3") (pinfunction "3_3") (pintype "passive"))
      (node (ref "VT2") (pin "3") (pinfunction "E_3") (pintype "passive"))
    )
    (net (code "20") (name "GND_II") (class "Default")
      (node (ref "L1") (pin "5") (pinfunction "5_5") (pintype "passive"))
      (node (ref "L1") (pin "6") (pinfunction "6_6") (pintype "passive"))
      (node (ref "L1") (pin "7") (pinfunction "7_7") (pintype "passive"))
      (node (ref "L1") (pin "8") (pinfunction "8_8") (pintype "passive"))
      (node (ref "U3") (pin "5") (pinfunction "VEE_5") (pintype "power_in"))
      (node (ref "VD3") (pin "1") (pinfunction "1_1") (pintype "passive"))
      (node (ref "VT1") (pin "3") (pinfunction "E_3") (pintype "passive"))
    )
    (net (code "21") (name "GND_III") (class "Default")
      (node (ref "U1") (pin "2") (pinfunction "GND_2") (pintype "passive"))
    )
    (net (code "22") (name "Net-(C1-+)") (class "Default")
      (node (ref "C1") (pin "1") (pinfunction "+_1") (pintype "passive"))
      (node (ref "C2") (pin "1") (pinfunction "+_1") (pintype "passive"))
      (node (ref "U1") (pin "4") (pinfunction "+IP_4") (pintype "passive"))
      (node (ref "VD1") (pin "1") (pinfunction "1_1") (pintype "passive"))
      (node (ref "VD2") (pin "1") (pinfunction "1_1") (pintype "passive"))
    )
    (net (code "23") (name "Net-(C1--)") (class "Default")
      (node (ref "C1") (pin "2") (pinfunction "-_2") (pintype "passive"))
      (node (ref "C4") (pin "1") (pinfunction "+_1") (pintype "passive"))
    )
    (net (code "24") (name "Net-(C2--)") (class "Default")
      (node (ref "C2") (pin "2") (pinfunction "-_2") (pintype "passive"))
      (node (ref "C5") (pin "1") (pinfunction "+_1") (pintype "passive"))
    )
    (net (code "25") (name "Net-(D1-K)") (class "Default")
      (node (ref "D1") (pin "1") (pinfunction "K_1") (pintype "passive"))
      (node (ref "D2") (pin "1") (pinfunction "K_1") (pintype "passive"))
      (node (ref "D3") (pin "1") (pinfunction "K_1") (pintype "passive"))
      (node (ref "J7") (pin "1") (pinfunction "0_1") (pintype "passive"))
      (node (ref "P2") (pin "1") (pinfunction "1_1") (pintype "passive"))
    )
    (net (code "26") (name "Net-(J1-17)") (class "Default")
      (node (ref "C3") (pin "2") (pinfunction "2_2") (pintype "passive"))
      (node (ref "J1") (pin "1") (pinfunction "17_1") (pintype "passive"))
      (node (ref "U2") (pin "4") (pinfunction "+IP_4") (pintype "passive"))
    )
    (net (code "27") (name "Net-(J2-17)") (class "Default")
      (node (ref "J2") (pin "1") (pinfunction "17_1") (pintype "passive"))
      (node (ref "R1") (pin "2") (pinfunction "2_2") (pintype "passive"))
      (node (ref "U1") (pin "5") (pinfunction "-IP_5") (pintype "passive"))
    )
    (net (code "28") (name "Net-(R1-Pad1)") (class "Default")
      (node (ref "R1") (pin "1") (pinfunction "1_1") (pintype "passive"))
      (node (ref "R4") (pin "2") (pinfunction "2_2") (pintype "passive"))
    )
    (net (code "29") (name "Net-(R2-Pad1)") (class "Default")
      (node (ref "R2") (pin "1") (pinfunction "1_1") (pintype "passive"))
      (node (ref "R5") (pin "2") (pinfunction "2_2") (pintype "passive"))
    )
    (net (code "30") (name "Net-(R3-Pad1)") (class "Default")
      (node (ref "R3") (pin "1") (pinfunction "1_1") (pintype "passive"))
      (node (ref "U3") (pin "6") (pinfunction "VO_6") (pintype "output"))
      (node (ref "U3") (pin "7") (pinfunction "VO_7") (pintype "output"))
    )
    (net (code "31") (name "Net-(R4-Pad1)") (class "Default")
      (node (ref "R4") (pin "1") (pinfunction "1_1") (pintype "passive"))
      (node (ref "R6") (pin "2") (pinfunction "2_2") (pintype "passive"))
    )
    (net (code "32") (name "Net-(R5-Pad1)") (class "Default")
      (node (ref "R5") (pin "1") (pinfunction "1_1") (pintype "passive"))
      (node (ref "R7") (pin "2") (pinfunction "2_2") (pintype "passive"))
    )
    (net (code "33") (name "Net-(R10-Pad1)") (class "Default")
      (node (ref "R10") (pin "1") (pinfunction "1_1") (pintype "passive"))
      (node (ref "U4") (pin "6") (pinfunction "VO_6") (pintype "output"))
      (node (ref "U4") (pin "7") (pinfunction "VO_7") (pintype "output"))
    )
    (net (code "34") (name "Net-(R11-Pad1)") (class "Default")
      (node (ref "R11") (pin "1") (pinfunction "1_1") (pintype "passive"))
      (node (ref "R13") (pin "2") (pinfunction "2_2") (pintype "passive"))
    )
    (net (code "35") (name "Net-(R13-Pad1)") (class "Default")
      (node (ref "R13") (pin "1") (pinfunction "1_1") (pintype "passive"))
      (node (ref "R16") (pin "2") (pinfunction "2_2") (pintype "passive"))
    )
    (net (code "36") (name "Net-(R24-Pad1)") (class "Default")
      (node (ref "R24") (pin "1") (pinfunction "1_1") (pintype "passive"))
      (node (ref "R26") (pin "2") (pinfunction "2_2") (pintype "passive"))
    )
    (net (code "37") (name "Net-(R26-Pad1)") (class "Default")
      (node (ref "R26") (pin "1") (pinfunction "1_1") (pintype "passive"))
      (node (ref "R29") (pin "2") (pinfunction "2_2") (pintype "passive"))
    )
    (net (code "38") (name "Net-(R37-Pad1)") (class "Default")
      (node (ref "R37") (pin "1") (pinfunction "1_1") (pintype "passive"))
      (node (ref "R39") (pin "2") (pinfunction "2_2") (pintype "passive"))
    )
    (net (code "39") (name "Net-(R39-Pad1)") (class "Default")
      (node (ref "R39") (pin "1") (pinfunction "1_1") (pintype "passive"))
      (node (ref "R42") (pin "2") (pinfunction "2_2") (pintype "passive"))
    )
    (net (code "40") (name "Net-(U2--IP)") (class "Default")
      (node (ref "R2") (pin "2") (pinfunction "2_2") (pintype "passive"))
      (node (ref "U2") (pin "5") (pinfunction "-IP_5") (pintype "passive"))
      (node (ref "VT1") (pin "2") (pinfunction "C_2") (pintype "passive"))
    )
    (net (code "41") (name "Net-(U5-VIN+)") (class "Default")
      (node (ref "C9") (pin "2") (pinfunction "2_2") (pintype "passive"))
      (node (ref "R12") (pin "2") (pinfunction "2_2") (pintype "passive"))
      (node (ref "R15") (pin "1") (pinfunction "1_1") (pintype "passive"))
      (node (ref "R16") (pin "1") (pinfunction "1_1") (pintype "passive"))
      (node (ref "R18") (pin "2") (pinfunction "2_2") (pintype "passive"))
      (node (ref "R19") (pin "2") (pinfunction "2_2") (pintype "passive"))
      (node (ref "U5") (pin "3") (pinfunction "VIN+_3") (pintype "input"))
      (node (ref "VD4") (pin "2") (pinfunction "C_2") (pintype "passive"))
      (node (ref "VD5") (pin "1") (pinfunction "C_1") (pintype "passive"))
    )
    (net (code "42") (name "Net-(U5-VIN-)") (class "Default")
      (node (ref "C10") (pin "2") (pinfunction "2_2") (pintype "passive"))
      (node (ref "R14") (pin "1") (pinfunction "1_1") (pintype "passive"))
      (node (ref "R21") (pin "2") (pinfunction "2_2") (pintype "passive"))
      (node (ref "U5") (pin "4") (pinfunction "VIN-_4") (pintype "input"))
      (node (ref "U6") (pin "1") (pinfunction "C_1") (pintype "passive"))
      (node (ref "U6") (pin "2") (pinfunction "REF_2") (pintype "passive"))
    )
    (net (code "43") (name "Net-(U5-VOUT)") (class "Default")
      (node (ref "C11") (pin "2") (pinfunction "2_2") (pintype "passive"))
      (node (ref "R17") (pin "2") (pinfunction "2_2") (pintype "passive"))
      (node (ref "R20") (pin "2") (pinfunction "2_2") (pintype "passive"))
      (node (ref "U5") (pin "1") (pinfunction "VOUT_1") (pintype "output"))
    )
    (net (code "44") (name "Net-(U7-VIN+)") (class "Default")
      (node (ref "C16") (pin "2") (pinfunction "2_2") (pintype "passive"))
      (node (ref "R25") (pin "2") (pinfunction "2_2") (pintype "passive"))
      (node (ref "R28") (pin "1") (pinfunction "1_1") (pintype "passive"))
      (node (ref "R29") (pin "1") (pinfunction "1_1") (pintype "passive"))
      (node (ref "R31") (pin "2") (pinfunction "2_2") (pintype "passive"))
      (node (ref "R32") (pin "2") (pinfunction "2_2") (pintype "passive"))
      (node (ref "U7") (pin "3") (pinfunction "VIN+_3") (pintype "input"))
      (node (ref "VD11") (pin "2") (pinfunction "C_2") (pintype "passive"))
      (node (ref "VD12") (pin "1") (pinfunction "C_1") (pintype "passive"))
    )
    (net (code "45") (name "Net-(U7-VIN-)") (class "Default")
      (node (ref "C17") (pin "2") (pinfunction "2_2") (pintype "passive"))
      (node (ref "R27") (pin "1") (pinfunction "1_1") (pintype "passive"))
      (node (ref "R34") (pin "2") (pinfunction "2_2") (pintype "passive"))
      (node (ref "U7") (pin "4") (pinfunction "VIN-_4") (pintype "input"))
      (node (ref "U8") (pin "1") (pinfunction "C_1") (pintype "passive"))
      (node (ref "U8") (pin "2") (pinfunction "REF_2") (pintype "passive"))
    )
    (net (code "46") (name "Net-(U7-VOUT)") (class "Default")
      (node (ref "C18") (pin "2") (pinfunction "2_2") (pintype "passive"))
      (node (ref "R30") (pin "2") (pinfunction "2_2") (pintype "passive"))
      (node (ref "R33") (pin "2") (pinfunction "2_2") (pintype "passive"))
      (node (ref "U7") (pin "1") (pinfunction "VOUT_1") (pintype "output"))
    )
    (net (code "47") (name "Net-(U9-VIN+)") (class "Default")
      (node (ref "C23") (pin "2") (pinfunction "2_2") (pintype "passive"))
      (node (ref "R38") (pin "2") (pinfunction "2_2") (pintype "passive"))
      (node (ref "R41") (pin "1") (pinfunction "1_1") (pintype "passive"))
      (node (ref "R42") (pin "1") (pinfunction "1_1") (pintype "passive"))
      (node (ref "R44") (pin "2") (pinfunction "2_2") (pintype "passive"))
      (node (ref "R45") (pin "2") (pinfunction "2_2") (pintype "passive"))
      (node (ref "U9") (pin "3") (pinfunction "VIN+_3") (pintype "input"))
      (node (ref "VD18") (pin "2") (pinfunction "C_2") (pintype "passive"))
      (node (ref "VD19") (pin "1") (pinfunction "C_1") (pintype "passive"))
    )
    (net (code "48") (name "Net-(U9-VOUT)") (class "Default")
      (node (ref "C25") (pin "2") (pinfunction "2_2") (pintype "passive"))
      (node (ref "R43") (pin "2") (pinfunction "2_2") (pintype "passive"))
      (node (ref "R46") (pin "2") (pinfunction "2_2") (pintype "passive"))
      (node (ref "U9") (pin "1") (pinfunction "VOUT_1") (pintype "output"))
    )
    (net (code "49") (name "Net-(U10-C)") (class "Default")
      (node (ref "C24") (pin "2") (pinfunction "2_2") (pintype "passive"))
      (node (ref "R40") (pin "1") (pinfunction "1_1") (pintype "passive"))
      (node (ref "R47") (pin "2") (pinfunction "2_2") (pintype "passive"))
      (node (ref "U10") (pin "1") (pinfunction "C_1") (pintype "passive"))
      (node (ref "U10") (pin "2") (pinfunction "REF_2") (pintype "passive"))
      (node (ref "U9") (pin "4") (pinfunction "VIN-_4") (pintype "input"))
    )
    (net (code "50") (name "Net-(VT1-G)") (class "Default")
      (node (ref "R3") (pin "2") (pinfunction "2_2") (pintype "passive"))
      (node (ref "VT1") (pin "1") (pinfunction "G_1") (pintype "passive"))
    )
    (net (code "51") (name "Net-(VT2-C)") (class "Default")
      (node (ref "L1") (pin "1") (pinfunction "1_1") (pintype "passive"))
      (node (ref "L1") (pin "2") (pinfunction "2_2") (pintype "passive"))
      (node (ref "L1") (pin "3") (pinfunction "3_3") (pintype "passive"))
      (node (ref "L1") (pin "4") (pinfunction "4_4") (pintype "passive"))
      (node (ref "VD1") (pin "3") (pinfunction "3_3") (pintype "passive"))
      (node (ref "VD2") (pin "3") (pinfunction "3_3") (pintype "passive"))
      (node (ref "VT2") (pin "2") (pinfunction "C_2") (pintype "passive"))
    )
    (net (code "52") (name "Net-(VT2-G)") (class "Default")
      (node (ref "R10") (pin "2") (pinfunction "2_2") (pintype "passive"))
      (node (ref "VT2") (pin "1") (pinfunction "G_1") (pintype "passive"))
    )
    (net (code "53") (name "unconnected-(U1-+VCC-Pad1)") (class "Default")
      (node (ref "U1") (pin "1") (pinfunction "+VCC_1") (pintype "passive"))
    )
    (net (code "54") (name "unconnected-(U1-OUT-Pad3)") (class "Default")
      (node (ref "U1") (pin "3") (pinfunction "OUT_3") (pintype "passive"))
    )
    (net (code "55") (name "unconnected-(U2-+VCC-Pad1)") (class "Default")
      (node (ref "U2") (pin "1") (pinfunction "+VCC_1") (pintype "passive"))
    )
    (net (code "56") (name "unconnected-(U2-GND-Pad2)") (class "Default")
      (node (ref "U2") (pin "2") (pinfunction "GND_2") (pintype "passive"))
    )
    (net (code "57") (name "unconnected-(U2-OUT-Pad3)") (class "Default")
      (node (ref "U2") (pin "3") (pinfunction "OUT_3") (pintype "passive"))
    )
    (net (code "58") (name "unconnected-(U3-NC-Pad1)") (class "Default")
      (node (ref "U3") (pin "1") (pinfunction "NC_1") (pintype "passive"))
    )
    (net (code "59") (name "unconnected-(U3-NC-Pad4)") (class "Default")
      (node (ref "U3") (pin "4") (pinfunction "NC_4") (pintype "passive"))
    )
    (net (code "60") (name "unconnected-(U4-NC-Pad1)") (class "Default")
      (node (ref "U4") (pin "1") (pinfunction "NC_1") (pintype "passive"))
    )
    (net (code "61") (name "unconnected-(U4-NC-Pad4)") (class "Default")
      (node (ref "U4") (pin "4") (pinfunction "NC_4") (pintype "passive"))
    )
  )
)
